# MotorConnect.net
KiCad netlist of a schematic drawn in Altium Designer
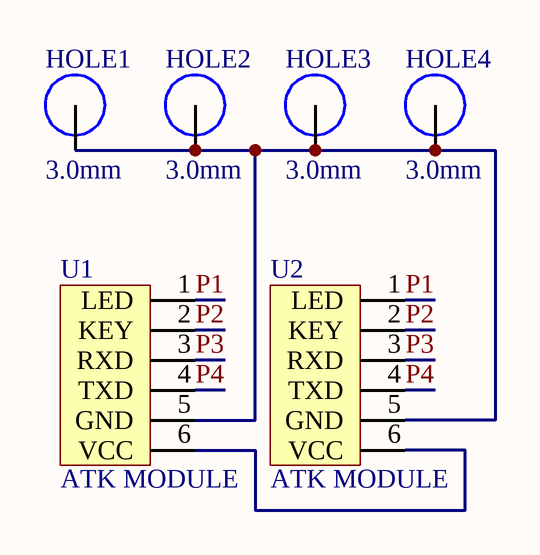
[diagram p0: MotorConnect.SchDoc]

(export (version "E")
  (design (tool "Eeschema 10.0.6"))
  (components
    (comp (ref "HOLE1")
      (value "3.0mm")
      (footprint "HOLE-M3")
      (fields (field (name "Comment") "HOLE"))
      (libsource (lib "YS_BDC_V1") (part "HOLE"))
    )
    (comp (ref "HOLE2")
      (value "3.0mm")
      (footprint "HOLE-M3")
      (fields (field (name "Comment") "HOLE"))
      (libsource (lib "YS_BDC_V1") (part "HOLE"))
    )
    (comp (ref "HOLE3")
      (value "3.0mm")
      (footprint "HOLE-M3")
      (fields (field (name "Comment") "HOLE"))
      (libsource (lib "YS_BDC_V1") (part "HOLE"))
    )
    (comp (ref "HOLE4")
      (value "3.0mm")
      (footprint "HOLE-M3")
      (fields (field (name "Comment") "HOLE"))
      (libsource (lib "YS_BDC_V1") (part "HOLE"))
    )
    (comp (ref "U1")
      (value "ATK MODULE")
      (footprint "HDR2.54-M-LI-6P")
      (description "ATK-HC05")
      (libsource (lib "阿波罗STM32F4&F7&H7底板封装库") (part "ATK-HC05"))
    )
    (comp (ref "U2")
      (value "ATK MODULE")
      (footprint "HDR2.54-M-LI-6P")
      (description "ATK-HC05")
      (libsource (lib "阿波罗STM32F4&F7&H7底板封装库") (part "ATK-HC05"))
    )
  )
  (nets
    (net (code "1") (name "/P1") (class "Default")
      (node (ref "U1") (pin "1") (pinfunction "LED_1") (pintype "passive"))
      (node (ref "U2") (pin "1") (pinfunction "LED_1") (pintype "passive"))
    )
    (net (code "2") (name "/P2") (class "Default")
      (node (ref "U1") (pin "2") (pinfunction "KEY_2") (pintype "passive"))
      (node (ref "U2") (pin "2") (pinfunction "KEY_2") (pintype "passive"))
    )
    (net (code "3") (name "/P3") (class "Default")
      (node (ref "U1") (pin "3") (pinfunction "RXD_3") (pintype "passive"))
      (node (ref "U2") (pin "3") (pinfunction "RXD_3") (pintype "passive"))
    )
    (net (code "4") (name "/P4") (class "Default")
      (node (ref "U1") (pin "4") (pinfunction "TXD_4") (pintype "passive"))
      (node (ref "U2") (pin "4") (pinfunction "TXD_4") (pintype "passive"))
    )
    (net (code "5") (name "Net-(U1-GND)") (class "Default")
      (node (ref "HOLE1") (pin "1") (pintype "passive"))
      (node (ref "HOLE2") (pin "1") (pintype "passive"))
      (node (ref "HOLE3") (pin "1") (pintype "passive"))
      (node (ref "HOLE4") (pin "1") (pintype "passive"))
      (node (ref "U1") (pin "5") (pinfunction "GND_5") (pintype "passive"))
      (node (ref "U2") (pin "5") (pinfunction "GND_5") (pintype "passive"))
    )
    (net (code "6") (name "Net-(U1-VCC)") (class "Default")
      (node (ref "U1") (pin "6") (pinfunction "VCC_6") (pintype "passive"))
      (node (ref "U2") (pin "6") (pinfunction "VCC_6") (pintype "passive"))
    )
  )
)
